# WCE_Battery_Bottom.net
KiCad netlist of a schematic drawn in Altium Designer
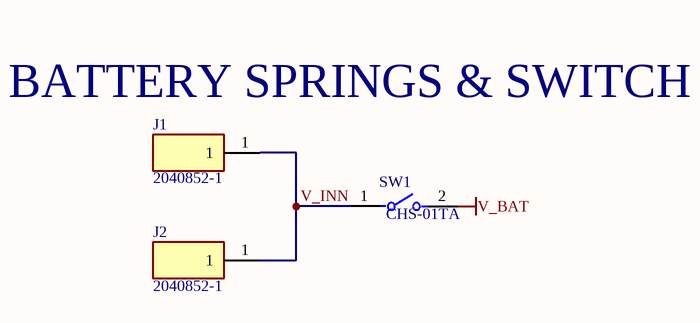
[diagram p0: WCE_Battery_Bottom.SchDoc]

(export (version "E")
  (design (tool "Eeschema 10.0.6"))
  (components
    (comp (ref "J1")
      (value "2040852-1")
      (footprint "2040852-1")
      (description "TE connectivity 2040852-1 PCB Spring Contact")
      (libsource (lib "WCE_thesis") (part "2040852-1"))
    )
    (comp (ref "J2")
      (value "2040852-1")
      (footprint "2040852-1")
      (description "TE connectivity 2040852-1 PCB Spring Contact")
      (libsource (lib "WCE_thesis") (part "2040852-1"))
    )
    (comp (ref "SW1")
      (value "CHS-01TA")
      (footprint "FP-CHS-01TA-MFG")
      (description "SWITCH SLIDE DIP SPST 100MA 6V")
      (fields
        (field (name "OCTOPART") "https://octopart.com/chs-01ta-nidec+copal-52304644")
        (field (name "MANUFACTURER") "Nidec Copal Electronics")
      )
      (libsource (lib "Altium Content Vault") (part "bb27bde45df87f1f469753f287ef5ae"))
    )
  )
  (nets
    (net (code "1") (name "/V_INN") (class "Default")
      (node (ref "J1") (pin "1") (pinfunction "1_1") (pintype "passive"))
      (node (ref "J2") (pin "1") (pinfunction "1_1") (pintype "passive"))
      (node (ref "SW1") (pin "1") (pinfunction "1_1") (pintype "passive"))
    )
    (net (code "2") (name "V_BAT") (class "Default")
      (node (ref "SW1") (pin "2") (pinfunction "2_2") (pintype "passive"))
    )
  )
)
